# can-ft_M2eeL9CoAo.net
KiCad netlist of a schematic drawn in EAGLE
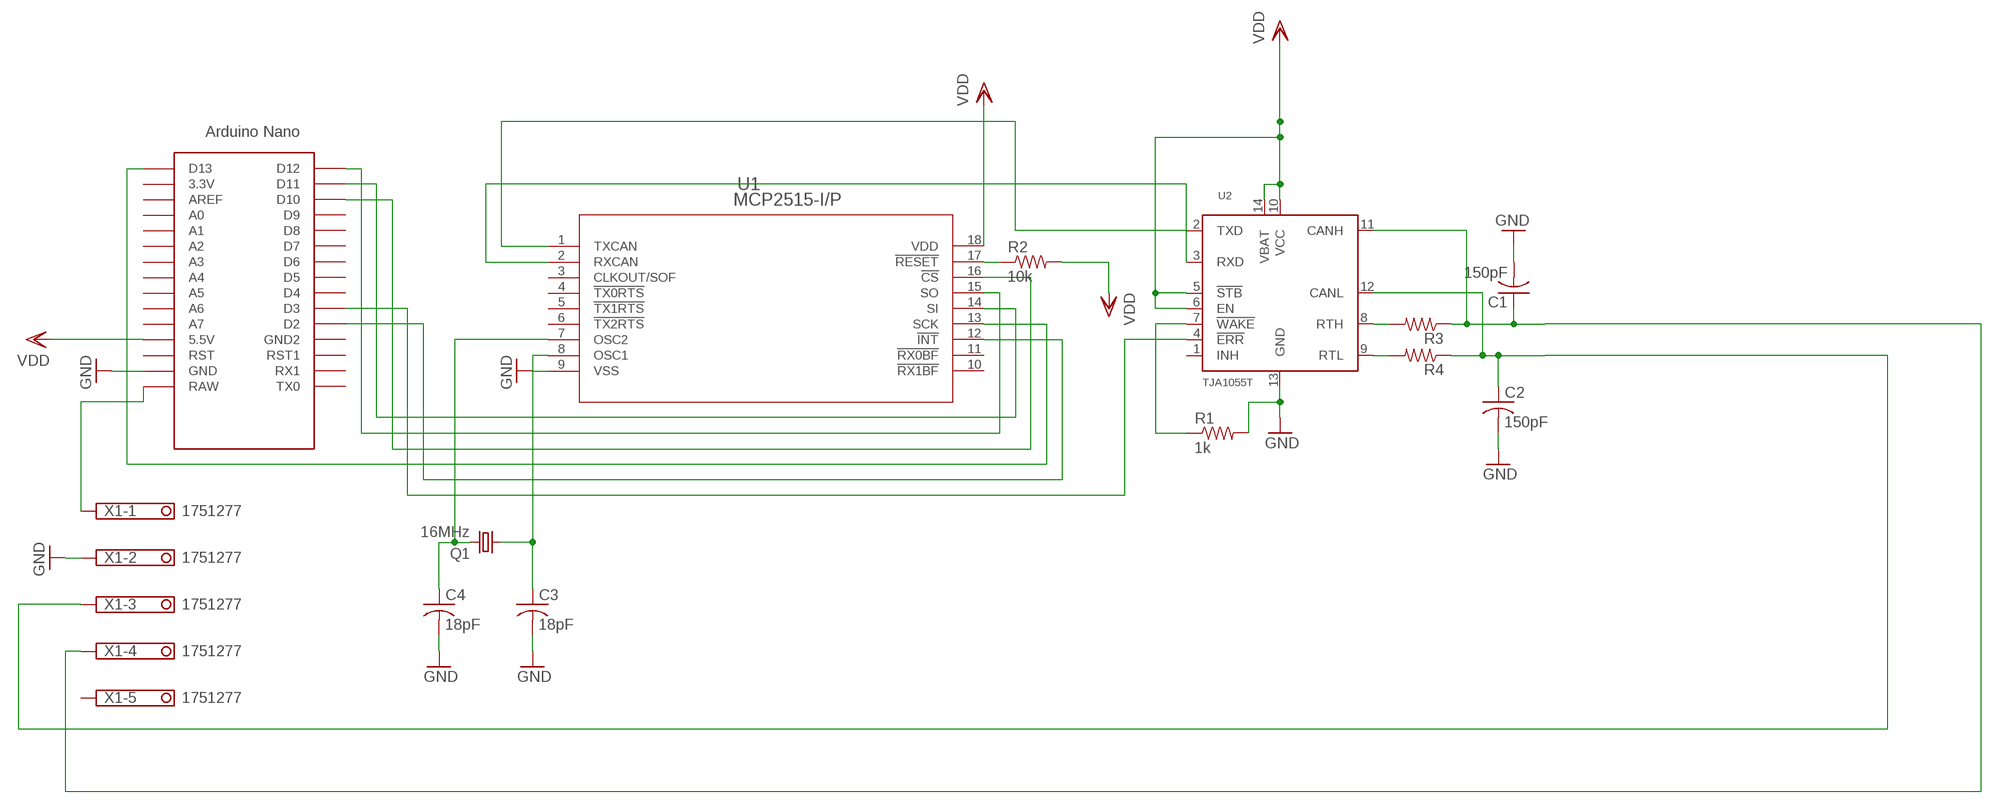
[diagram p0: schematic, sheet 1]

(export (version "E")
  (design (tool "Eeschema 10.0.6"))
  (components
    (comp (ref "C1")
      (value "150pF")
      (footprint "eagle-import:C050-025X075")
      (libsource (lib "eagle-import") (part "C-US050-025X075"))
    )
    (comp (ref "C2")
      (value "150pF")
      (footprint "eagle-import:C050-025X075")
      (libsource (lib "eagle-import") (part "C-US050-025X075"))
    )
    (comp (ref "C3")
      (value "18pF")
      (footprint "eagle-import:C050-025X075")
      (libsource (lib "eagle-import") (part "C-US050-025X075"))
    )
    (comp (ref "C4")
      (value "18pF")
      (footprint "eagle-import:C050-025X075")
      (libsource (lib "eagle-import") (part "C-US050-025X075"))
    )
    (comp (ref "Q1")
      (value "16MHz")
      (footprint "eagle-import:HC49_S")
      (libsource (lib "eagle-import") (part "CRYSTALHC49S"))
    )
    (comp (ref "R1")
      (value "1k")
      (footprint "eagle-import:0207_7")
      (libsource (lib "eagle-import") (part "R-US_0207/7"))
    )
    (comp (ref "R2")
      (value "10k")
      (footprint "eagle-import:0207_7")
      (libsource (lib "eagle-import") (part "R-US_0207/7"))
    )
    (comp (ref "R3")
      (value "R-US_0207/7")
      (footprint "eagle-import:0207_7")
      (libsource (lib "eagle-import") (part "R-US_0207/7"))
    )
    (comp (ref "R4")
      (value "R-US_0207/7")
      (footprint "eagle-import:0207_7")
      (libsource (lib "eagle-import") (part "R-US_0207/7"))
    )
    (comp (ref "U$1")
      (value "NANO")
      (footprint "eagle-import:NANO")
      (libsource (lib "eagle-import") (part "NANO"))
    )
    (comp (ref "U1")
      (value "MCP2515-I/P")
      (footprint "eagle-import:PDIP18_300MC_MCH")
      (libsource (lib "eagle-import") (part "MCP2515-I/P"))
    )
    (comp (ref "U2")
      (value "TJA1055T")
      (footprint "eagle-import:SOT108-1")
      (libsource (lib "eagle-import") (part "TJA1055T"))
    )
    (comp (ref "X1")
      (value "1751277")
      (footprint "eagle-import:1751277")
      (libsource (lib "eagle-import") (part "1751277"))
    )
  )
  (nets
    (net (code "1") (name "GND") (class "Default")
      (node (ref "C1") (pin "2") (pinfunction "2_2") (pintype "passive"))
      (node (ref "C2") (pin "2") (pinfunction "2_2") (pintype "passive"))
      (node (ref "C3") (pin "2") (pinfunction "2_2") (pintype "passive"))
      (node (ref "C4") (pin "2") (pinfunction "2_2") (pintype "passive"))
      (node (ref "R1") (pin "2") (pinfunction "2_2") (pintype "passive"))
      (node (ref "U$1") (pin "GND") (pinfunction "GND_GND") (pintype "bidirectional"))
      (node (ref "U1") (pin "9") (pinfunction "VSS_9") (pintype "passive"))
      (node (ref "U2") (pin "13") (pinfunction "GND_13") (pintype "power_in"))
      (node (ref "X1") (pin "2") (pinfunction "K_2") (pintype "passive"))
    )
    (net (code "2") (name "Net-(U1-OSC1)") (class "Default")
      (node (ref "C3") (pin "1") (pinfunction "1_1") (pintype "passive"))
      (node (ref "Q1") (pin "1") (pinfunction "1_1") (pintype "passive"))
      (node (ref "U1") (pin "8") (pinfunction "OSC1_8") (pintype "passive"))
    )
    (net (code "3") (name "Net-(U1-OSC2)") (class "Default")
      (node (ref "C4") (pin "1") (pinfunction "1_1") (pintype "passive"))
      (node (ref "Q1") (pin "2") (pinfunction "2_2") (pintype "passive"))
      (node (ref "U1") (pin "7") (pinfunction "OSC2_7") (pintype "passive"))
    )
    (net (code "4") (name "Net-(U1-RXCAN)") (class "Default")
      (node (ref "U1") (pin "2") (pinfunction "RXCAN_2") (pintype "passive"))
      (node (ref "U2") (pin "3") (pinfunction "RXD_3") (pintype "bidirectional"))
    )
    (net (code "5") (name "Net-(U1-SCK)") (class "Default")
      (node (ref "U$1") (pin "D13") (pinfunction "D13_D13") (pintype "bidirectional"))
      (node (ref "U1") (pin "13") (pinfunction "SCK_13") (pintype "passive"))
    )
    (net (code "6") (name "Net-(U1-SI)") (class "Default")
      (node (ref "U$1") (pin "D11") (pinfunction "D11_D11") (pintype "bidirectional"))
      (node (ref "U1") (pin "14") (pinfunction "SI_14") (pintype "passive"))
    )
    (net (code "7") (name "Net-(U1-SO)") (class "Default")
      (node (ref "U$1") (pin "D12") (pinfunction "D12_D12") (pintype "bidirectional"))
      (node (ref "U1") (pin "15") (pinfunction "SO_15") (pintype "passive"))
    )
    (net (code "8") (name "Net-(U1-TXCAN)") (class "Default")
      (node (ref "U1") (pin "1") (pinfunction "TXCAN_1") (pintype "passive"))
      (node (ref "U2") (pin "2") (pinfunction "TXD_2") (pintype "output"))
    )
    (net (code "9") (name "Net-(U1-~{CS})") (class "Default")
      (node (ref "U$1") (pin "D10") (pinfunction "D10_D10") (pintype "bidirectional"))
      (node (ref "U1") (pin "16") (pinfunction "~{CS}_16") (pintype "passive"))
    )
    (net (code "10") (name "Net-(U1-~{INT})") (class "Default")
      (node (ref "U$1") (pin "D2") (pinfunction "D2_D2") (pintype "bidirectional"))
      (node (ref "U1") (pin "12") (pinfunction "~{INT}_12") (pintype "passive"))
    )
    (net (code "11") (name "Net-(U1-~{RESET})") (class "Default")
      (node (ref "R2") (pin "1") (pinfunction "1_1") (pintype "passive"))
      (node (ref "U1") (pin "17") (pinfunction "~{RESET}_17") (pintype "passive"))
    )
    (net (code "12") (name "Net-(U2-CANH)") (class "Default")
      (node (ref "C1") (pin "1") (pinfunction "1_1") (pintype "passive"))
      (node (ref "R3") (pin "1") (pinfunction "1_1") (pintype "passive"))
      (node (ref "U2") (pin "11") (pinfunction "CANH_11") (pintype "bidirectional"))
      (node (ref "X1") (pin "4") (pinfunction "K_4") (pintype "passive"))
    )
    (net (code "13") (name "Net-(U2-CANL)") (class "Default")
      (node (ref "C2") (pin "1") (pinfunction "1_1") (pintype "passive"))
      (node (ref "R4") (pin "1") (pinfunction "1_1") (pintype "passive"))
      (node (ref "U2") (pin "12") (pinfunction "CANL_12") (pintype "bidirectional"))
      (node (ref "X1") (pin "3") (pinfunction "K_3") (pintype "passive"))
    )
    (net (code "14") (name "Net-(U2-RTH)") (class "Default")
      (node (ref "R3") (pin "2") (pinfunction "2_2") (pintype "passive"))
      (node (ref "U2") (pin "8") (pinfunction "RTH_8") (pintype "passive"))
    )
    (net (code "15") (name "Net-(U2-RTL)") (class "Default")
      (node (ref "R4") (pin "2") (pinfunction "2_2") (pintype "passive"))
      (node (ref "U2") (pin "9") (pinfunction "RTL_9") (pintype "passive"))
    )
    (net (code "16") (name "Net-(U2-~{ERR})") (class "Default")
      (node (ref "U$1") (pin "D3") (pinfunction "D3_D3") (pintype "bidirectional"))
      (node (ref "U2") (pin "4") (pinfunction "~{ERR}_4") (pintype "output"))
    )
    (net (code "17") (name "Net-(U2-~{WAKE})") (class "Default")
      (node (ref "R1") (pin "1") (pinfunction "1_1") (pintype "passive"))
      (node (ref "U2") (pin "7") (pinfunction "~{WAKE}_7") (pintype "input"))
    )
    (net (code "18") (name "Net-(X1A-K)") (class "Default")
      (node (ref "U$1") (pin "RAW") (pinfunction "RAW_RAW") (pintype "bidirectional"))
      (node (ref "X1") (pin "1") (pinfunction "K_1") (pintype "passive"))
    )
    (net (code "19") (name "VDD") (class "Default")
      (node (ref "R2") (pin "2") (pinfunction "2_2") (pintype "passive"))
      (node (ref "U$1") (pin "5V") (pinfunction "5.5V_5V") (pintype "bidirectional"))
      (node (ref "U1") (pin "18") (pinfunction "VDD_18") (pintype "passive"))
      (node (ref "U2") (pin "10") (pinfunction "VCC_10") (pintype "power_in"))
      (node (ref "U2") (pin "14") (pinfunction "VBAT_14") (pintype "power_in"))
      (node (ref "U2") (pin "5") (pinfunction "~{STB}_5") (pintype "input"))
      (node (ref "U2") (pin "6") (pinfunction "EN_6") (pintype "input"))
    )
    (net (code "20") (name "unconnected-(U$1-GND2-PadGND1)") (class "Default")
      (node (ref "U$1") (pin "GND1") (pinfunction "GND2_GND1") (pintype "bidirectional"))
    )
    (net (code "21") (name "unconnected-(U$1-Pad3.3V)") (class "Default")
      (node (ref "U$1") (pin "3.3V") (pinfunction "3.3V_3.3V") (pintype "bidirectional"))
    )
    (net (code "22") (name "unconnected-(U$1-PadA0)") (class "Default")
      (node (ref "U$1") (pin "A0") (pinfunction "A0_A0") (pintype "bidirectional"))
    )
    (net (code "23") (name "unconnected-(U$1-PadA1)") (class "Default")
      (node (ref "U$1") (pin "A1") (pinfunction "A1_A1") (pintype "bidirectional"))
    )
    (net (code "24") (name "unconnected-(U$1-PadA2)") (class "Default")
      (node (ref "U$1") (pin "A2") (pinfunction "A2_A2") (pintype "bidirectional"))
    )
    (net (code "25") (name "unconnected-(U$1-PadA3)") (class "Default")
      (node (ref "U$1") (pin "A3") (pinfunction "A3_A3") (pintype "bidirectional"))
    )
    (net (code "26") (name "unconnected-(U$1-PadA4)") (class "Default")
      (node (ref "U$1") (pin "A4") (pinfunction "A4_A4") (pintype "bidirectional"))
    )
    (net (code "27") (name "unconnected-(U$1-PadA5)") (class "Default")
      (node (ref "U$1") (pin "A5") (pinfunction "A5_A5") (pintype "bidirectional"))
    )
    (net (code "28") (name "unconnected-(U$1-PadA6)") (class "Default")
      (node (ref "U$1") (pin "A6") (pinfunction "A6_A6") (pintype "bidirectional"))
    )
    (net (code "29") (name "unconnected-(U$1-PadA7)") (class "Default")
      (node (ref "U$1") (pin "A7") (pinfunction "A7_A7") (pintype "bidirectional"))
    )
    (net (code "30") (name "unconnected-(U$1-PadAREF)") (class "Default")
      (node (ref "U$1") (pin "AREF") (pinfunction "AREF_AREF") (pintype "bidirectional"))
    )
    (net (code "31") (name "unconnected-(U$1-PadD4)") (class "Default")
      (node (ref "U$1") (pin "D4") (pinfunction "D4_D4") (pintype "bidirectional"))
    )
    (net (code "32") (name "unconnected-(U$1-PadD5)") (class "Default")
      (node (ref "U$1") (pin "D5") (pinfunction "D5_D5") (pintype "bidirectional"))
    )
    (net (code "33") (name "unconnected-(U$1-PadD6)") (class "Default")
      (node (ref "U$1") (pin "D6") (pinfunction "D6_D6") (pintype "bidirectional"))
    )
    (net (code "34") (name "unconnected-(U$1-PadD7)") (class "Default")
      (node (ref "U$1") (pin "D7") (pinfunction "D7_D7") (pintype "bidirectional"))
    )
    (net (code "35") (name "unconnected-(U$1-PadD8)") (class "Default")
      (node (ref "U$1") (pin "D8") (pinfunction "D8_D8") (pintype "bidirectional"))
    )
    (net (code "36") (name "unconnected-(U$1-PadD9)") (class "Default")
      (node (ref "U$1") (pin "D9") (pinfunction "D9_D9") (pintype "bidirectional"))
    )
    (net (code "37") (name "unconnected-(U$1-PadICSP1)") (class "Default")
      (node (ref "U$1") (pin "ICSP1") (pinfunction "ICSP1_ICSP1") (pintype "bidirectional"))
    )
    (net (code "38") (name "unconnected-(U$1-PadICSP2)") (class "Default")
      (node (ref "U$1") (pin "ICSP2") (pinfunction "ICSP2_ICSP2") (pintype "bidirectional"))
    )
    (net (code "39") (name "unconnected-(U$1-PadICSP3)") (class "Default")
      (node (ref "U$1") (pin "ICSP3") (pinfunction "ICSP3_ICSP3") (pintype "bidirectional"))
    )
    (net (code "40") (name "unconnected-(U$1-PadICSP4)") (class "Default")
      (node (ref "U$1") (pin "ICSP4") (pinfunction "ICSP4_ICSP4") (pintype "bidirectional"))
    )
    (net (code "41") (name "unconnected-(U$1-PadICSP5)") (class "Default")
      (node (ref "U$1") (pin "ICSP5") (pinfunction "ICSP5_ICSP5") (pintype "bidirectional"))
    )
    (net (code "42") (name "unconnected-(U$1-PadICSP6)") (class "Default")
      (node (ref "U$1") (pin "ICSP6") (pinfunction "ICSP6_ICSP6") (pintype "bidirectional"))
    )
    (net (code "43") (name "unconnected-(U$1-PadRST)") (class "Default")
      (node (ref "U$1") (pin "RST") (pinfunction "RST_RST") (pintype "bidirectional"))
    )
    (net (code "44") (name "unconnected-(U$1-PadRST1)") (class "Default")
      (node (ref "U$1") (pin "RST1") (pinfunction "RST1_RST1") (pintype "bidirectional"))
    )
    (net (code "45") (name "unconnected-(U$1-PadRX1)") (class "Default")
      (node (ref "U$1") (pin "RX1") (pinfunction "RX1_RX1") (pintype "bidirectional"))
    )
    (net (code "46") (name "unconnected-(U$1-PadTX0)") (class "Default")
      (node (ref "U$1") (pin "TX0") (pinfunction "TX0_TX0") (pintype "bidirectional"))
    )
    (net (code "47") (name "unconnected-(U1-CLKOUT{slash}SOF-Pad3)") (class "Default")
      (node (ref "U1") (pin "3") (pinfunction "CLKOUT/SOF_3") (pintype "passive"))
    )
    (net (code "48") (name "unconnected-(U1-~{RX0BF}-Pad11)") (class "Default")
      (node (ref "U1") (pin "11") (pinfunction "~{RX0BF}_11") (pintype "passive"))
    )
    (net (code "49") (name "unconnected-(U1-~{RX1BF}-Pad10)") (class "Default")
      (node (ref "U1") (pin "10") (pinfunction "~{RX1BF}_10") (pintype "passive"))
    )
    (net (code "50") (name "unconnected-(U1-~{TX0RTS}-Pad4)") (class "Default")
      (node (ref "U1") (pin "4") (pinfunction "~{TX0RTS}_4") (pintype "passive"))
    )
    (net (code "51") (name "unconnected-(U1-~{TX1RTS}-Pad5)") (class "Default")
      (node (ref "U1") (pin "5") (pinfunction "~{TX1RTS}_5") (pintype "passive"))
    )
    (net (code "52") (name "unconnected-(U1-~{TX2RTS}-Pad6)") (class "Default")
      (node (ref "U1") (pin "6") (pinfunction "~{TX2RTS}_6") (pintype "passive"))
    )
    (net (code "53") (name "unconnected-(U2-INH-Pad1)") (class "Default")
      (node (ref "U2") (pin "1") (pinfunction "INH_1") (pintype "input"))
    )
    (net (code "54") (name "unconnected-(X1E-K-Pad5)") (class "Default")
      (node (ref "X1") (pin "5") (pinfunction "K_5") (pintype "passive"))
    )
  )
)
